# Port_21_04_33.net
KiCad netlist of a schematic drawn in Altium Designer
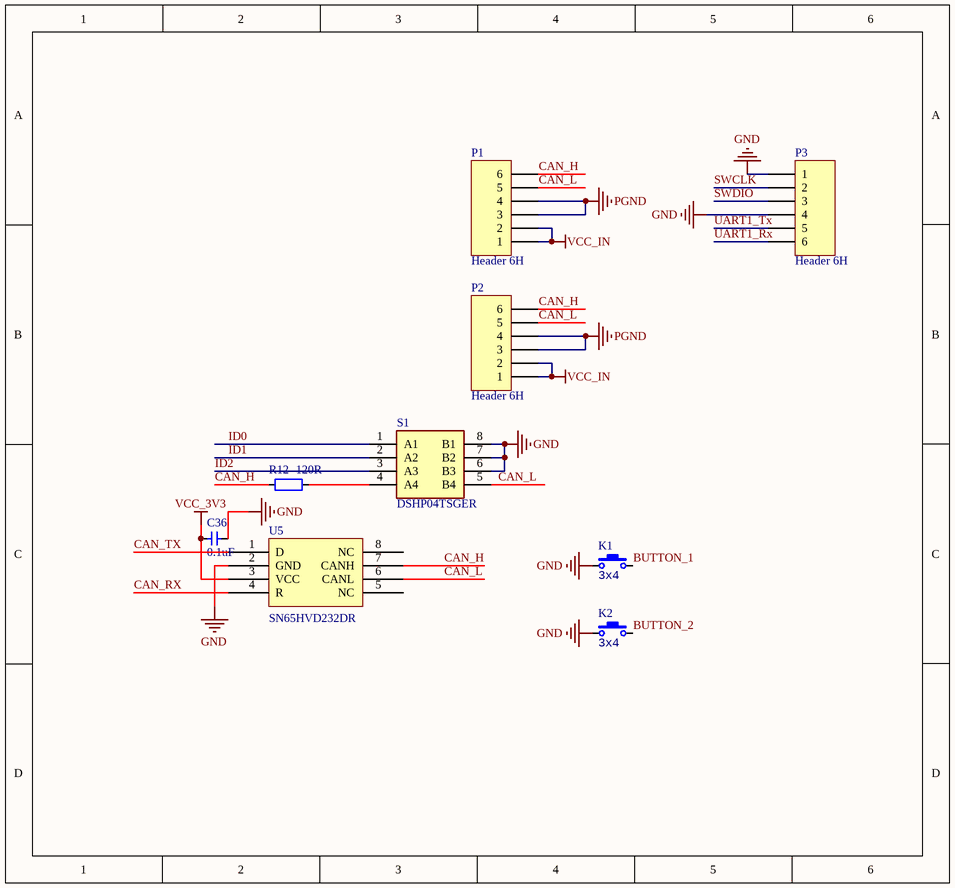
[diagram p0: Port 21.04.33.SchDoc]

(export (version "E")
  (design (tool "Eeschema 10.0.6"))
  (components
    (comp (ref "C36")
      (value "0.1uF")
      (footprint "motor42-lib:CAP_0402")
      (description "Capacitor")
      (libsource (lib "MyPcbLib") (part "电容-0402"))
    )
    (comp (ref "K1")
      (value "3x4")
      (footprint "ButtonTACT_3x4x2_180")
      (description "Button")
      (fields (field (name "Comment") "TACT 2P"))
      (libsource (lib "KitSprout") (part "ButtonTACT_3x4x2_180"))
    )
    (comp (ref "K2")
      (value "3x4")
      (footprint "ButtonTACT_3x4x2_180")
      (description "Button")
      (fields (field (name "Comment") "TACT 2P"))
      (libsource (lib "KitSprout") (part "ButtonTACT_3x4x2_180"))
    )
    (comp (ref "P1")
      (value "Header 6H")
      (footprint "CONN-TH_HC-ZH1.5-6A-s")
      (description "Header, 6-Pin, Right Angle")
      (fields (field (name "PUBLISHER") "Altium Limited"))
      (libsource (lib "Miscellaneous Connectors") (part "Header 6H"))
    )
    (comp (ref "P2")
      (value "Header 6H")
      (footprint "CONN-TH_HC-ZH1.5-6A-s")
      (description "Header, 6-Pin, Right Angle")
      (fields (field (name "PUBLISHER") "Altium Limited"))
      (libsource (lib "Miscellaneous Connectors") (part "Header 6H"))
    )
    (comp (ref "P3")
      (value "Header 6H")
      (footprint "CONN-TH_HC-ZH1.5-6A-s")
      (description "Header, 6-Pin, Right Angle")
      (fields (field (name "PUBLISHER") "Altium Limited"))
      (libsource (lib "") (part "Header 6H_1"))
    )
    (comp (ref "R12")
      (value "120R")
      (footprint "RES_0402")
      (description "Resistor")
      (libsource (lib "MyPcbLib") (part "电阻-0402"))
    )
    (comp (ref "S1")
      (value "DSHP04TSGER")
      (footprint "SW-SMD_DSHP04TS-S")
      (description "DIP Switches / SIP Switches 4 pos. low profile Btm Seal Tape J Bend")
      (fields
        (field (name "MOUSER PART NUMBER") "774-218-4LPSTJ")
        (field (name "MANUFACTURER_PART_NUMBER") "218-4LPSTJ")
      )
      (libsource (lib "Schlib1") (part "218-4LPSTJ"))
    )
    (comp (ref "U5")
      (value "SN65HVD232D")
      (footprint "so-8")
      (fields
        (field (name "MANUFACTURER") "Texas Instruments")
        (field (name "MANUFACTURER PART NUMBER") "SN65HVD232DR")
      )
      (libsource (lib "MyPcbLib") (part "SN65HVD232D"))
    )
  )
  (nets
    (net (code "1") (name "/BUTTON_1") (class "Default")
      (node (ref "K1") (pin "2") (pinfunction "2_2") (pintype "passive"))
    )
    (net (code "2") (name "/BUTTON_2") (class "Default")
      (node (ref "K2") (pin "2") (pinfunction "2_2") (pintype "passive"))
    )
    (net (code "3") (name "/CAN_H") (class "Default")
      (node (ref "P1") (pin "6") (pinfunction "6_6") (pintype "passive"))
      (node (ref "P2") (pin "6") (pinfunction "6_6") (pintype "passive"))
      (node (ref "R12") (pin "1") (pinfunction "1_1") (pintype "passive"))
      (node (ref "U5") (pin "7") (pinfunction "CANH_7") (pintype "passive"))
    )
    (net (code "4") (name "/CAN_L") (class "Default")
      (node (ref "P1") (pin "5") (pinfunction "5_5") (pintype "passive"))
      (node (ref "P2") (pin "5") (pinfunction "5_5") (pintype "passive"))
      (node (ref "S1") (pin "5") (pinfunction "B4_5") (pintype "passive"))
      (node (ref "U5") (pin "6") (pinfunction "CANL_6") (pintype "passive"))
    )
    (net (code "5") (name "/CAN_RX") (class "Default")
      (node (ref "U5") (pin "4") (pinfunction "R_4") (pintype "passive"))
    )
    (net (code "6") (name "/CAN_TX") (class "Default")
      (node (ref "U5") (pin "1") (pinfunction "D_1") (pintype "passive"))
    )
    (net (code "7") (name "/ID0") (class "Default")
      (node (ref "S1") (pin "1") (pinfunction "A1_1") (pintype "passive"))
    )
    (net (code "8") (name "/ID1") (class "Default")
      (node (ref "S1") (pin "2") (pinfunction "A2_2") (pintype "passive"))
    )
    (net (code "9") (name "/ID2") (class "Default")
      (node (ref "S1") (pin "3") (pinfunction "A3_3") (pintype "passive"))
    )
    (net (code "10") (name "/SWCLK") (class "Default")
      (node (ref "P3") (pin "2") (pinfunction "2_2") (pintype "passive"))
    )
    (net (code "11") (name "/SWDIO") (class "Default")
      (node (ref "P3") (pin "3") (pinfunction "3_3") (pintype "passive"))
    )
    (net (code "12") (name "/UART1_Rx") (class "Default")
      (node (ref "P3") (pin "6") (pinfunction "6_6") (pintype "passive"))
    )
    (net (code "13") (name "/UART1_Tx") (class "Default")
      (node (ref "P3") (pin "5") (pinfunction "5_5") (pintype "passive"))
    )
    (net (code "14") (name "GND") (class "Default")
      (node (ref "C36") (pin "1") (pinfunction "1_1") (pintype "passive"))
      (node (ref "K1") (pin "1") (pinfunction "1_1") (pintype "passive"))
      (node (ref "K2") (pin "1") (pinfunction "1_1") (pintype "passive"))
      (node (ref "P3") (pin "1") (pinfunction "1_1") (pintype "passive"))
      (node (ref "P3") (pin "4") (pinfunction "4_4") (pintype "passive"))
      (node (ref "S1") (pin "6") (pinfunction "B3_6") (pintype "passive"))
      (node (ref "S1") (pin "7") (pinfunction "B2_7") (pintype "passive"))
      (node (ref "S1") (pin "8") (pinfunction "B1_8") (pintype "passive"))
      (node (ref "U5") (pin "2") (pinfunction "GND_2") (pintype "passive"))
    )
    (net (code "15") (name "Net-(S1-A4)") (class "Default")
      (node (ref "R12") (pin "2") (pinfunction "2_2") (pintype "passive"))
      (node (ref "S1") (pin "4") (pinfunction "A4_4") (pintype "passive"))
    )
    (net (code "16") (name "PGND") (class "Default")
      (node (ref "P1") (pin "3") (pinfunction "3_3") (pintype "passive"))
      (node (ref "P1") (pin "4") (pinfunction "4_4") (pintype "passive"))
      (node (ref "P2") (pin "3") (pinfunction "3_3") (pintype "passive"))
      (node (ref "P2") (pin "4") (pinfunction "4_4") (pintype "passive"))
    )
    (net (code "17") (name "VCC_3V3") (class "Default")
      (node (ref "C36") (pin "2") (pinfunction "2_2") (pintype "passive"))
      (node (ref "U5") (pin "3") (pinfunction "VCC_3") (pintype "passive"))
    )
    (net (code "18") (name "VCC_IN") (class "Default")
      (node (ref "P1") (pin "1") (pinfunction "1_1") (pintype "passive"))
      (node (ref "P1") (pin "2") (pinfunction "2_2") (pintype "passive"))
      (node (ref "P2") (pin "1") (pinfunction "1_1") (pintype "passive"))
      (node (ref "P2") (pin "2") (pinfunction "2_2") (pintype "passive"))
    )
    (net (code "19") (name "unconnected-(U5-NC-Pad5)") (class "Default")
      (node (ref "U5") (pin "5") (pinfunction "NC_5") (pintype "passive"))
    )
    (net (code "20") (name "unconnected-(U5-NC-Pad8)") (class "Default")
      (node (ref "U5") (pin "8") (pinfunction "NC_8") (pintype "passive"))
    )
  )
)
